# AND.net
KiCad netlist of a schematic drawn in EAGLE
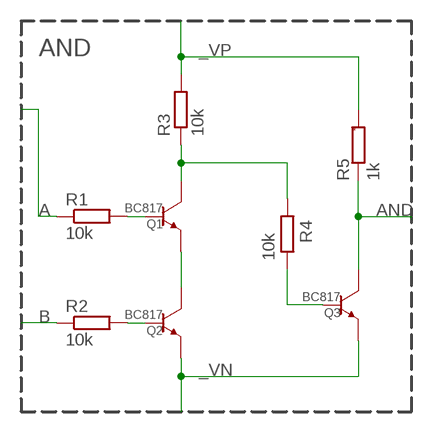
[diagram p0: schematic, sheet 1]

(export (version "E")
  (design (tool "Eeschema 10.0.6"))
  (components
    (comp (ref "Q1")
      (value "BC817")
      (footprint "eagle-import:SOT23")
      (libsource (lib "eagle-import") (part "TRANSISTOR-NPN-GENERIC-SOT23-BECDEFAULT"))
    )
    (comp (ref "Q2")
      (value "BC817")
      (footprint "eagle-import:SOT23")
      (libsource (lib "eagle-import") (part "TRANSISTOR-NPN-GENERIC-SOT23-BECDEFAULT"))
    )
    (comp (ref "Q3")
      (value "BC817")
      (footprint "eagle-import:SOT23")
      (libsource (lib "eagle-import") (part "TRANSISTOR-NPN-GENERIC-SOT23-BECDEFAULT"))
    )
    (comp (ref "R1")
      (value "10k")
      (footprint "eagle-import:R0603")
      (libsource (lib "eagle-import") (part "R-EU_R0603"))
    )
    (comp (ref "R2")
      (value "10k")
      (footprint "eagle-import:R0603")
      (libsource (lib "eagle-import") (part "R-EU_R0603"))
    )
    (comp (ref "R3")
      (value "10k")
      (footprint "eagle-import:R0603")
      (libsource (lib "eagle-import") (part "R-EU_R0603"))
    )
    (comp (ref "R4")
      (value "10k")
      (footprint "eagle-import:R0603")
      (libsource (lib "eagle-import") (part "R-EU_R0603"))
    )
    (comp (ref "R5")
      (value "1k")
      (footprint "eagle-import:R0603-MARK")
      (libsource (lib "eagle-import") (part "R-EU-MARKEDR0603"))
    )
  )
  (nets
    (net (code "1") (name "/A") (class "Default")
      (node (ref "R1") (pin "1") (pinfunction "1_1") (pintype "passive"))
    )
    (net (code "2") (name "/AND") (class "Default")
      (node (ref "Q3") (pin "P$3") (pinfunction "COLLECTOR_P$3") (pintype "bidirectional"))
      (node (ref "R5") (pin "1") (pinfunction "1_1") (pintype "passive"))
    )
    (net (code "3") (name "/B") (class "Default")
      (node (ref "R2") (pin "1") (pinfunction "1_1") (pintype "passive"))
    )
    (net (code "4") (name "/_VN") (class "Default")
      (node (ref "Q2") (pin "P$2") (pinfunction "EMITTER_P$2") (pintype "bidirectional"))
      (node (ref "Q3") (pin "P$2") (pinfunction "EMITTER_P$2") (pintype "bidirectional"))
    )
    (net (code "5") (name "/_VP") (class "Default")
      (node (ref "R3") (pin "2") (pinfunction "2_2") (pintype "passive"))
      (node (ref "R5") (pin "2") (pinfunction "2_2") (pintype "passive"))
    )
    (net (code "6") (name "Net-(Q1-BASE)") (class "Default")
      (node (ref "Q1") (pin "P$1") (pinfunction "BASE_P$1") (pintype "bidirectional"))
      (node (ref "R1") (pin "2") (pinfunction "2_2") (pintype "passive"))
    )
    (net (code "7") (name "Net-(Q1-COLLECTOR)") (class "Default")
      (node (ref "Q1") (pin "P$3") (pinfunction "COLLECTOR_P$3") (pintype "bidirectional"))
      (node (ref "R3") (pin "1") (pinfunction "1_1") (pintype "passive"))
      (node (ref "R4") (pin "2") (pinfunction "2_2") (pintype "passive"))
    )
    (net (code "8") (name "Net-(Q1-EMITTER)") (class "Default")
      (node (ref "Q1") (pin "P$2") (pinfunction "EMITTER_P$2") (pintype "bidirectional"))
      (node (ref "Q2") (pin "P$3") (pinfunction "COLLECTOR_P$3") (pintype "bidirectional"))
    )
    (net (code "9") (name "Net-(Q2-BASE)") (class "Default")
      (node (ref "Q2") (pin "P$1") (pinfunction "BASE_P$1") (pintype "bidirectional"))
      (node (ref "R2") (pin "2") (pinfunction "2_2") (pintype "passive"))
    )
    (net (code "10") (name "Net-(Q3-BASE)") (class "Default")
      (node (ref "Q3") (pin "P$1") (pinfunction "BASE_P$1") (pintype "bidirectional"))
      (node (ref "R4") (pin "1") (pinfunction "1_1") (pintype "passive"))
    )
  )
)
